# Power.net
KiCad netlist of a schematic drawn in Altium Designer
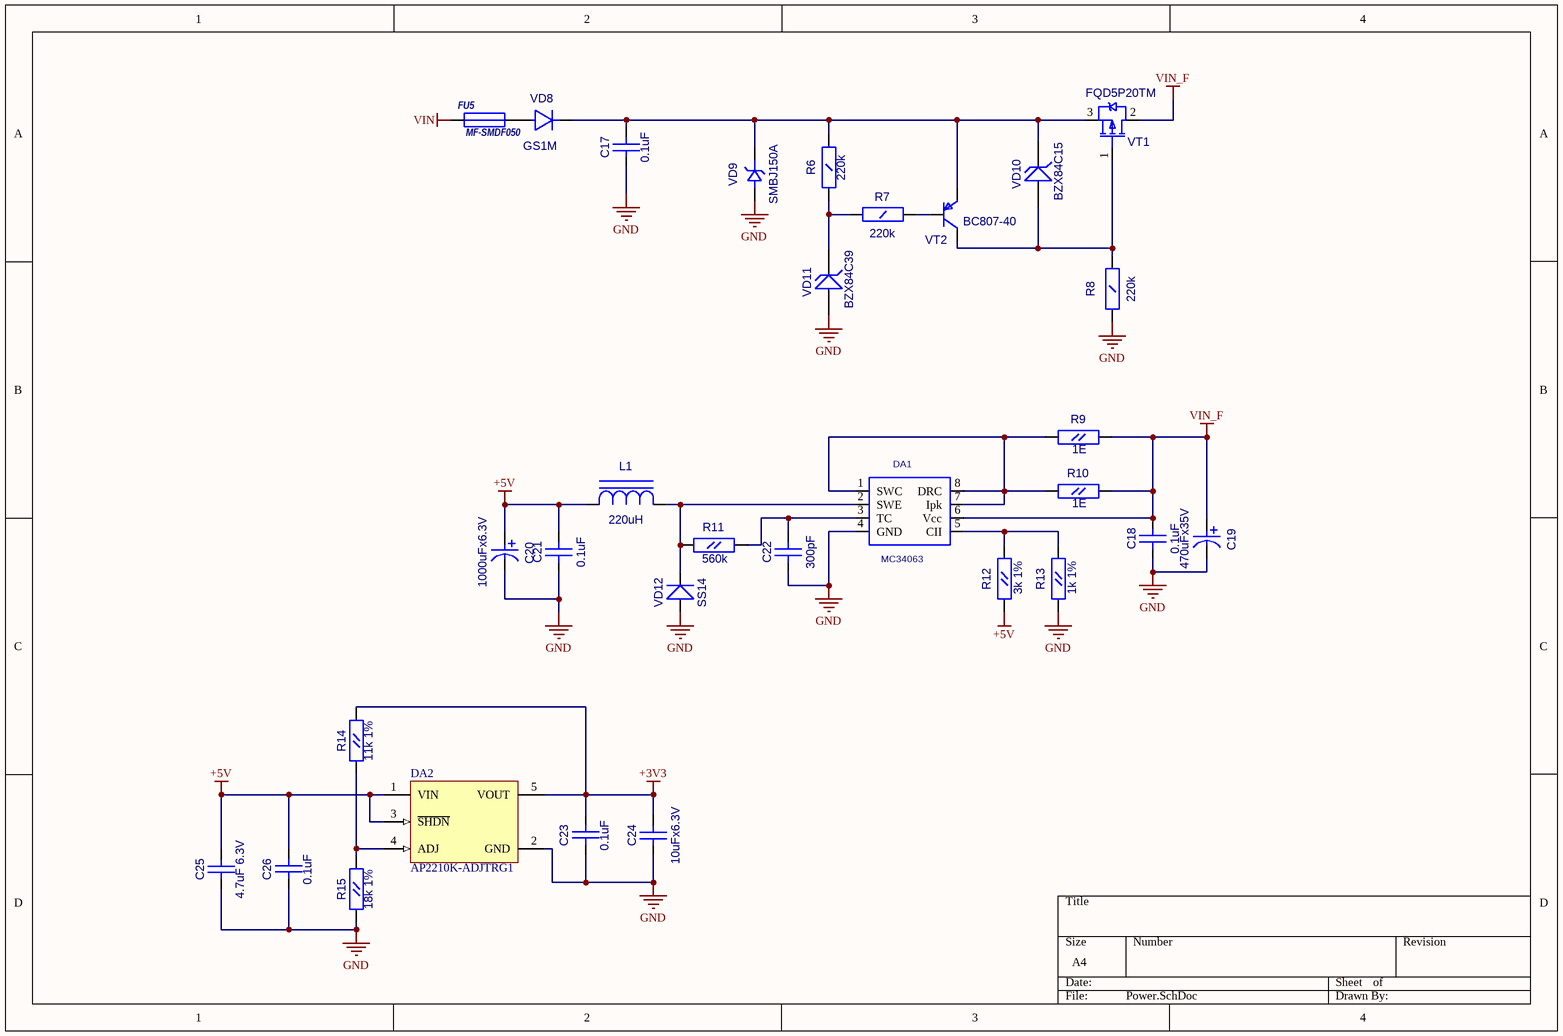
[diagram p0: Power.SchDoc]

(export (version "E")
  (design (tool "Eeschema 10.0.6"))
  (components
    (comp (ref "C17")
      (value "0.1uF")
      (footprint "CC1206")
      (description "CC1206")
      (libsource (lib "gprs_modem_2") (part "CC1206"))
    )
    (comp (ref "C18")
      (value "0.1uF")
      (footprint "CC0603")
      (description "CC0603")
      (libsource (lib "gprs_modem_2") (part "CC0603"))
    )
    (comp (ref "C19")
      (value "470uFx35V")
      (footprint "CC16X10_CAP0.5(1)(Primary)")
      (description "CAP0.5(1)")
      (libsource (lib "gprs_modem_2") (part "CAP0.5(1)"))
    )
    (comp (ref "C20")
      (value "1000uFx6.3V")
      (footprint "CC8X3.5")
      (description "CAP0.35")
      (libsource (lib "gprs_modem_2") (part "CAP0.35"))
    )
    (comp (ref "C21")
      (value "0.1uF")
      (footprint "CC0603")
      (description "CC0603")
      (libsource (lib "gprs_modem_2") (part "CC0603"))
    )
    (comp (ref "C22")
      (value "300pF")
      (footprint "CC0603")
      (description "CC0603")
      (libsource (lib "gprs_modem_2") (part "CC0603"))
    )
    (comp (ref "C23")
      (value "0.1uF")
      (footprint "CC0603")
      (description "CC0603")
      (libsource (lib "gprs_modem_2") (part "CC0603"))
    )
    (comp (ref "C24")
      (value "10uFx6.3V")
      (footprint "CC0805")
      (description "CC0805")
      (libsource (lib "gprs_modem_2") (part "CC0805"))
    )
    (comp (ref "C25")
      (value "4.7uF 6.3V")
      (footprint "CC0805")
      (description "CC0805")
      (libsource (lib "gprs_modem_2") (part "CC0805"))
    )
    (comp (ref "C26")
      (value "0.1uF")
      (footprint "CC0603")
      (description "CC0603")
      (libsource (lib "gprs_modem_2") (part "CC0603"))
    )
    (comp (ref "DA1") (value "MC34063") (footprint "SO-8") (libsource (lib "Schetchik") (part "MC34063")))
    (comp (ref "DA2")
      (value "AP2210K-ADJTRG1")
      (footprint "SOT23-5")
      (fields (field (name "PUBLISHER") "Altium Limited"))
      (libsource (lib "gprs_modem_2") (part "MCP1824T-ADJE/OT"))
    )
    (comp (ref "FU5")
      (value "MF-SMDF050")
      (footprint "MF-SMDF")
      (description "MF-SMDF")
      (libsource (lib "gprs_modem_2") (part "MF-SMDF"))
    )
    (comp (ref "L1")
      (value "220uH")
      (footprint "SDR0805")
      (description "SDR0805")
      (libsource (lib "gprs_modem_2") (part "SDR0805"))
    )
    (comp (ref "R6")
      (value "220k")
      (footprint "RC1206")
      (description "RC1206")
      (libsource (lib "gprs_modem_2") (part "RC1206"))
    )
    (comp (ref "R7")
      (value "220k")
      (footprint "RC1206")
      (description "RC1206")
      (libsource (lib "gprs_modem_2") (part "RC1206"))
    )
    (comp (ref "R8")
      (value "220k")
      (footprint "RC1206")
      (description "RC1206")
      (libsource (lib "gprs_modem_2") (part "RC1206"))
    )
    (comp (ref "R9")
      (value "1E")
      (footprint "RC0805")
      (description "RC0805")
      (libsource (lib "gprs_modem_2") (part "RC0805"))
    )
    (comp (ref "R10")
      (value "1E")
      (footprint "RC0805")
      (description "RC0805")
      (libsource (lib "gprs_modem_2") (part "RC0805"))
    )
    (comp (ref "R11")
      (value "560k")
      (footprint "RC0603")
      (description "RC0603")
      (libsource (lib "gprs_modem_2") (part "RC0603"))
    )
    (comp (ref "R12")
      (value "3k 1%")
      (footprint "RC0603")
      (description "RC0603")
      (libsource (lib "gprs_modem_2") (part "RC0603"))
    )
    (comp (ref "R13")
      (value "1k 1%")
      (footprint "RC0603")
      (description "RC0603")
      (libsource (lib "gprs_modem_2") (part "RC0603"))
    )
    (comp (ref "R14")
      (value "11k 1%")
      (footprint "RC0603")
      (description "RC0603")
      (libsource (lib "gprs_modem_2") (part "RC0603"))
    )
    (comp (ref "R15")
      (value "18k 1%")
      (footprint "RC0603")
      (description "RC0603")
      (libsource (lib "gprs_modem_2") (part "RC0603"))
    )
    (comp (ref "VD8") (value "GS1M") (footprint "SMA") (libsource (lib "gprs_modem") (part "GS1M")))
    (comp (ref "VD9")
      (value "SMBJ150A")
      (footprint "SMB")
      (description "SMBJ")
      (libsource (lib "gprs_modem_2") (part "SMBJ"))
    )
    (comp (ref "VD10")
      (value "BZX84C15")
      (footprint "SOT-23(123)")
      (description "Zener Voltage Regulator Diode")
      (libsource (lib "gprs_modem_2") (part "BZX84"))
    )
    (comp (ref "VD11")
      (value "BZX84C39")
      (footprint "SOT-23(123)")
      (description "Zener Voltage Regulator Diode")
      (libsource (lib "gprs_modem_2") (part "BZX84"))
    )
    (comp (ref "VD12")
      (value "SS14")
      (footprint "SMA")
      (description "Schottky Rectifier")
      (libsource (lib "gprs_modem_2") (part "SS14"))
    )
    (comp (ref "VT1")
      (value "FQD5P20TM")
      (footprint "D-PAK(TO-252AA)")
      (description "HEXFET Power MOSFET")
      (libsource (lib "gprs_modem_2") (part "IRFR9220"))
    )
    (comp (ref "VT2")
      (value "BC807-40")
      (footprint "SOT-23(123)")
      (description "BC857B")
      (libsource (lib "gprs_modem") (part "BC857B"))
    )
  )
  (nets
    (net (code "1") (name "+3V3") (class "Default")
      (node (ref "C23") (pin "1") (pinfunction "A_1") (pintype "passive"))
      (node (ref "C24") (pin "2") (pinfunction "B_2") (pintype "passive"))
      (node (ref "DA2") (pin "5") (pinfunction "VOUT_5") (pintype "power_in"))
      (node (ref "R14") (pin "2") (pinfunction "B_2") (pintype "passive"))
    )
    (net (code "2") (name "+5V") (class "Default")
      (node (ref "C20") (pin "1") (pintype "passive"))
      (node (ref "C21") (pin "2") (pinfunction "B_2") (pintype "passive"))
      (node (ref "C25") (pin "2") (pinfunction "B_2") (pintype "passive"))
      (node (ref "C26") (pin "1") (pinfunction "A_1") (pintype "passive"))
      (node (ref "DA2") (pin "1") (pinfunction "VIN_1") (pintype "power_in"))
      (node (ref "DA2") (pin "3") (pinfunction "~{SHDN}_3") (pintype "input"))
      (node (ref "L1") (pin "1") (pinfunction "C_1") (pintype "passive"))
      (node (ref "R12") (pin "1") (pinfunction "A_1") (pintype "passive"))
    )
    (net (code "3") (name "GND") (class "Default")
      (node (ref "C17") (pin "1") (pinfunction "A_1") (pintype "passive"))
      (node (ref "C18") (pin "1") (pinfunction "A_1") (pintype "passive"))
      (node (ref "C19") (pin "1") (pintype "passive"))
      (node (ref "C20") (pin "2") (pintype "passive"))
      (node (ref "C21") (pin "1") (pinfunction "A_1") (pintype "passive"))
      (node (ref "C22") (pin "1") (pinfunction "A_1") (pintype "passive"))
      (node (ref "C23") (pin "2") (pinfunction "B_2") (pintype "passive"))
      (node (ref "C24") (pin "1") (pinfunction "A_1") (pintype "passive"))
      (node (ref "C25") (pin "1") (pinfunction "A_1") (pintype "passive"))
      (node (ref "C26") (pin "2") (pinfunction "B_2") (pintype "passive"))
      (node (ref "DA1") (pin "4") (pinfunction "GND_4") (pintype "passive"))
      (node (ref "DA2") (pin "2") (pinfunction "GND_2") (pintype "power_in"))
      (node (ref "R13") (pin "1") (pinfunction "A_1") (pintype "passive"))
      (node (ref "R15") (pin "1") (pinfunction "A_1") (pintype "passive"))
      (node (ref "R8") (pin "2") (pinfunction "B_2") (pintype "passive"))
      (node (ref "VD11") (pin "1") (pinfunction "A_1") (pintype "passive"))
      (node (ref "VD12") (pin "1") (pinfunction "A_1") (pintype "passive"))
      (node (ref "VD9") (pin "1") (pinfunction "A_1") (pintype "passive"))
    )
    (net (code "4") (name "Net-(C17-B)") (class "Default")
      (node (ref "C17") (pin "2") (pinfunction "B_2") (pintype "passive"))
      (node (ref "R6") (pin "2") (pinfunction "B_2") (pintype "passive"))
      (node (ref "VD10") (pin "3") (pinfunction "K_3") (pintype "passive"))
      (node (ref "VD8") (pin "2") (pinfunction "K_2") (pintype "passive"))
      (node (ref "VD9") (pin "2") (pinfunction "K_2") (pintype "passive"))
      (node (ref "VT1") (pin "3") (pinfunction "S_3") (pintype "passive"))
      (node (ref "VT2") (pin "2") (pinfunction "E_2") (pintype "passive"))
    )
    (net (code "5") (name "Net-(C22-B)") (class "Default")
      (node (ref "C22") (pin "2") (pinfunction "B_2") (pintype "passive"))
      (node (ref "DA1") (pin "3") (pinfunction "TC_3") (pintype "passive"))
      (node (ref "R11") (pin "2") (pinfunction "B_2") (pintype "passive"))
    )
    (net (code "6") (name "Net-(DA1-CII)") (class "Default")
      (node (ref "DA1") (pin "5") (pinfunction "CII_5") (pintype "passive"))
      (node (ref "R12") (pin "2") (pinfunction "B_2") (pintype "passive"))
      (node (ref "R13") (pin "2") (pinfunction "B_2") (pintype "passive"))
    )
    (net (code "7") (name "Net-(DA1-DRC)") (class "Default")
      (node (ref "DA1") (pin "1") (pinfunction "SWC_1") (pintype "passive"))
      (node (ref "DA1") (pin "7") (pinfunction "Ipk_7") (pintype "passive"))
      (node (ref "DA1") (pin "8") (pinfunction "DRC_8") (pintype "passive"))
      (node (ref "R10") (pin "1") (pinfunction "A_1") (pintype "passive"))
      (node (ref "R9") (pin "1") (pinfunction "A_1") (pintype "passive"))
    )
    (net (code "8") (name "Net-(DA1-SWE)") (class "Default")
      (node (ref "DA1") (pin "2") (pinfunction "SWE_2") (pintype "passive"))
      (node (ref "L1") (pin "2") (pinfunction "A_2") (pintype "passive"))
      (node (ref "R11") (pin "1") (pinfunction "A_1") (pintype "passive"))
      (node (ref "VD12") (pin "2") (pinfunction "K_2") (pintype "passive"))
    )
    (net (code "9") (name "Net-(DA2-ADJ)") (class "Default")
      (node (ref "DA2") (pin "4") (pinfunction "ADJ_4") (pintype "input"))
      (node (ref "R14") (pin "1") (pinfunction "A_1") (pintype "passive"))
      (node (ref "R15") (pin "2") (pinfunction "B_2") (pintype "passive"))
    )
    (net (code "10") (name "Net-(R6-A)") (class "Default")
      (node (ref "R6") (pin "1") (pinfunction "A_1") (pintype "passive"))
      (node (ref "R7") (pin "1") (pinfunction "A_1") (pintype "passive"))
      (node (ref "VD11") (pin "3") (pinfunction "K_3") (pintype "passive"))
    )
    (net (code "11") (name "Net-(R7-B)") (class "Default")
      (node (ref "R7") (pin "2") (pinfunction "B_2") (pintype "passive"))
      (node (ref "VT2") (pin "1") (pinfunction "B_1") (pintype "passive"))
    )
    (net (code "12") (name "Net-(R8-A)") (class "Default")
      (node (ref "R8") (pin "1") (pinfunction "A_1") (pintype "passive"))
      (node (ref "VD10") (pin "1") (pinfunction "A_1") (pintype "passive"))
      (node (ref "VT1") (pin "1") (pinfunction "G_1") (pintype "passive"))
      (node (ref "VT2") (pin "3") (pinfunction "C_3") (pintype "passive"))
    )
    (net (code "13") (name "Net-(VD8-A)") (class "Default")
      (node (ref "FU5") (pin "2") (pintype "passive"))
      (node (ref "VD8") (pin "1") (pinfunction "A_1") (pintype "passive"))
    )
    (net (code "14") (name "VIN") (class "Default") (node (ref "FU5") (pin "1") (pintype "passive")))
    (net (code "15") (name "VIN_F") (class "Default")
      (node (ref "C18") (pin "2") (pinfunction "B_2") (pintype "passive"))
      (node (ref "C19") (pin "2") (pintype "passive"))
      (node (ref "DA1") (pin "6") (pinfunction "Vcc_6") (pintype "passive"))
      (node (ref "R10") (pin "2") (pinfunction "B_2") (pintype "passive"))
      (node (ref "R9") (pin "2") (pinfunction "B_2") (pintype "passive"))
      (node (ref "VT1") (pin "2") (pinfunction "D_2") (pintype "passive"))
    )
  )
)
